# display-header.net
KiCad netlist of a schematic drawn in Altium Designer
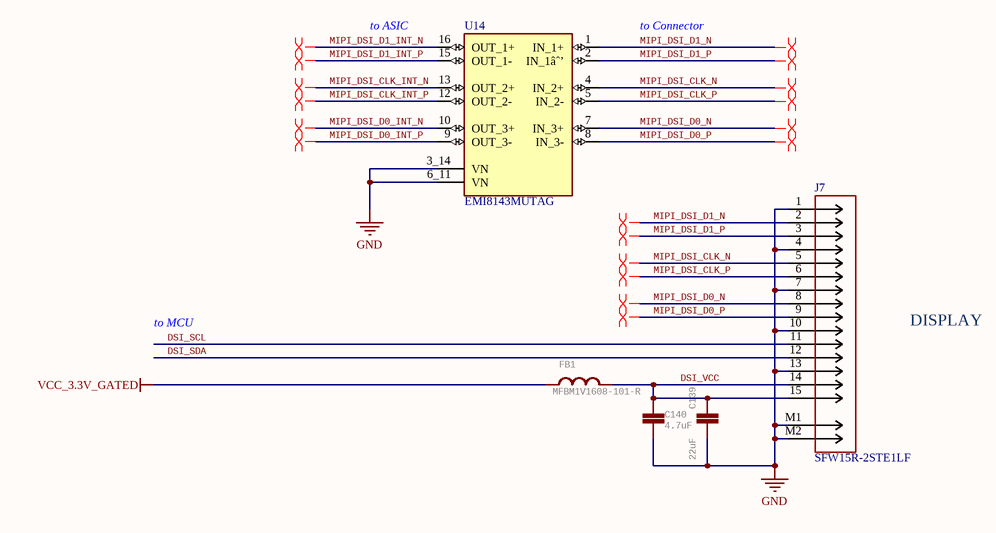
[diagram p0: display-header.SchDoc]

(export (version "E")
  (design (tool "Eeschema 10.0.6"))
  (components
    (comp (ref "C139")
      (value "22uF")
      (footprint "0805")
      (fields (field (name "MPN") "CL21A226MQQNNNE"))
      (libsource (lib "openmv-ae3") (part "22UF-0805-6.3V-20%"))
    )
    (comp (ref "C140")
      (value "4.7uF")
      (footprint "0402-CAP")
      (description "CapacitorStandard 0603 ceramic capacitor, and 0.1\" leaded capacitor.")
      (fields (field (name "MPN") "JMK105BBJ475MV-F") (field (name "LIBRARYNAME") "sfe"))
      (libsource (lib "openmv-ae3") (part "CAP0402-CAP"))
    )
    (comp (ref "FB1")
      (value "MFBM1V1608-101-R")
      (footprint "0603-RES")
      (libsource (lib "openmv-ae3") (part "INDUCTOR"))
    )
    (comp (ref "J7")
      (value "SFW15R-2STE1LF")
      (footprint "CON15_1X15_DRB_SFW_JAE")
      (description "No Description Available")
      (fields
        (field (name "MF") "JAE Electronics")
        (field (name "COPYRIGHT") "Copyright (C) 2023 Ultra Librarian. All rights reserved.")
      )
      (libsource (lib "openmv-ae3") (part "SFW15R-2STE1LF"))
    )
    (comp (ref "U14")
      (value "EMI8143MUTAG")
      (footprint "IC_EMI8143MUTAG")
      (description "6 Line Common Mode Choke Surface Mount 100mA DCR 6Ohm (Typ)")
      (fields
        (field (name "MF") "ON Semiconductor")
        (field (name "DIGI-KEY_PART_NUMBER") "EMI8143MUTAGOSCT-ND")
      )
      (libsource (lib "openmv-ae3") (part "CMP-008-000000-1"))
    )
  )
  (nets
    (net (code "1") (name "/DSI_SCL") (class "Default")
      (node (ref "J7") (pin "11") (pinfunction "11_11") (pintype "passive"))
    )
    (net (code "2") (name "/DSI_SDA") (class "Default")
      (node (ref "J7") (pin "12") (pinfunction "12_12") (pintype "passive"))
    )
    (net (code "3") (name "/DSI_VCC") (class "Default")
      (node (ref "C139") (pin "1") (pinfunction "1_1") (pintype "passive"))
      (node (ref "C140") (pin "2") (pinfunction "2_2") (pintype "passive"))
      (node (ref "FB1") (pin "2") (pinfunction "2_2") (pintype "passive"))
      (node (ref "J7") (pin "14") (pinfunction "14_14") (pintype "passive"))
      (node (ref "J7") (pin "15") (pinfunction "15_15") (pintype "passive"))
    )
    (net (code "4") (name "/MIPI_DSI_CLK_INT_N") (class "Default")
      (node (ref "U14") (pin "13") (pinfunction "OUT_2+_13") (pintype "bidirectional"))
    )
    (net (code "5") (name "/MIPI_DSI_CLK_INT_P") (class "Default")
      (node (ref "U14") (pin "12") (pinfunction "OUT_2-_12") (pintype "bidirectional"))
    )
    (net (code "6") (name "/MIPI_DSI_CLK_N") (class "Default")
      (node (ref "J7") (pin "5") (pinfunction "5_5") (pintype "passive"))
      (node (ref "U14") (pin "4") (pinfunction "IN_2+_4") (pintype "bidirectional"))
    )
    (net (code "7") (name "/MIPI_DSI_CLK_P") (class "Default")
      (node (ref "J7") (pin "6") (pinfunction "6_6") (pintype "passive"))
      (node (ref "U14") (pin "5") (pinfunction "IN_2-_5") (pintype "bidirectional"))
    )
    (net (code "8") (name "/MIPI_DSI_D0_INT_N") (class "Default")
      (node (ref "U14") (pin "10") (pinfunction "OUT_3+_10") (pintype "bidirectional"))
    )
    (net (code "9") (name "/MIPI_DSI_D0_INT_P") (class "Default")
      (node (ref "U14") (pin "9") (pinfunction "OUT_3-_9") (pintype "bidirectional"))
    )
    (net (code "10") (name "/MIPI_DSI_D0_N") (class "Default")
      (node (ref "J7") (pin "8") (pinfunction "8_8") (pintype "passive"))
      (node (ref "U14") (pin "7") (pinfunction "IN_3+_7") (pintype "bidirectional"))
    )
    (net (code "11") (name "/MIPI_DSI_D0_P") (class "Default")
      (node (ref "J7") (pin "9") (pinfunction "9_9") (pintype "passive"))
      (node (ref "U14") (pin "8") (pinfunction "IN_3-_8") (pintype "bidirectional"))
    )
    (net (code "12") (name "/MIPI_DSI_D1_INT_N") (class "Default")
      (node (ref "U14") (pin "16") (pinfunction "OUT_1+_16") (pintype "bidirectional"))
    )
    (net (code "13") (name "/MIPI_DSI_D1_INT_P") (class "Default")
      (node (ref "U14") (pin "15") (pinfunction "OUT_1-_15") (pintype "bidirectional"))
    )
    (net (code "14") (name "/MIPI_DSI_D1_N") (class "Default")
      (node (ref "J7") (pin "2") (pinfunction "2_2") (pintype "passive"))
      (node (ref "U14") (pin "1") (pinfunction "IN_1+_1") (pintype "bidirectional"))
    )
    (net (code "15") (name "/MIPI_DSI_D1_P") (class "Default")
      (node (ref "J7") (pin "3") (pinfunction "3_3") (pintype "passive"))
      (node (ref "U14") (pin "2") (pinfunction "IN_1âˆ’_2") (pintype "bidirectional"))
    )
    (net (code "16") (name "GND") (class "Default")
      (node (ref "C139") (pin "2") (pinfunction "2_2") (pintype "passive"))
      (node (ref "C140") (pin "1") (pinfunction "1_1") (pintype "passive"))
      (node (ref "J7") (pin "1") (pinfunction "1_1") (pintype "passive"))
      (node (ref "J7") (pin "10") (pinfunction "10_10") (pintype "passive"))
      (node (ref "J7") (pin "13") (pinfunction "13_13") (pintype "passive"))
      (node (ref "J7") (pin "4") (pinfunction "4_4") (pintype "passive"))
      (node (ref "J7") (pin "7") (pinfunction "7_7") (pintype "passive"))
      (node (ref "J7") (pin "M1") (pinfunction "16_M1") (pintype "passive"))
      (node (ref "J7") (pin "M2") (pinfunction "17_M2") (pintype "passive"))
      (node (ref "U14") (pin "3_14") (pinfunction "VN_3_14") (pintype "power_in"))
      (node (ref "U14") (pin "6_11") (pinfunction "VN_6_11") (pintype "power_in"))
    )
    (net (code "17") (name "VCC_3.3V_GATED") (class "Default")
      (node (ref "FB1") (pin "1") (pinfunction "1_1") (pintype "passive"))
    )
  )
)
